# EEM_Connectors.net
KiCad netlist of a schematic drawn in Altium Designer
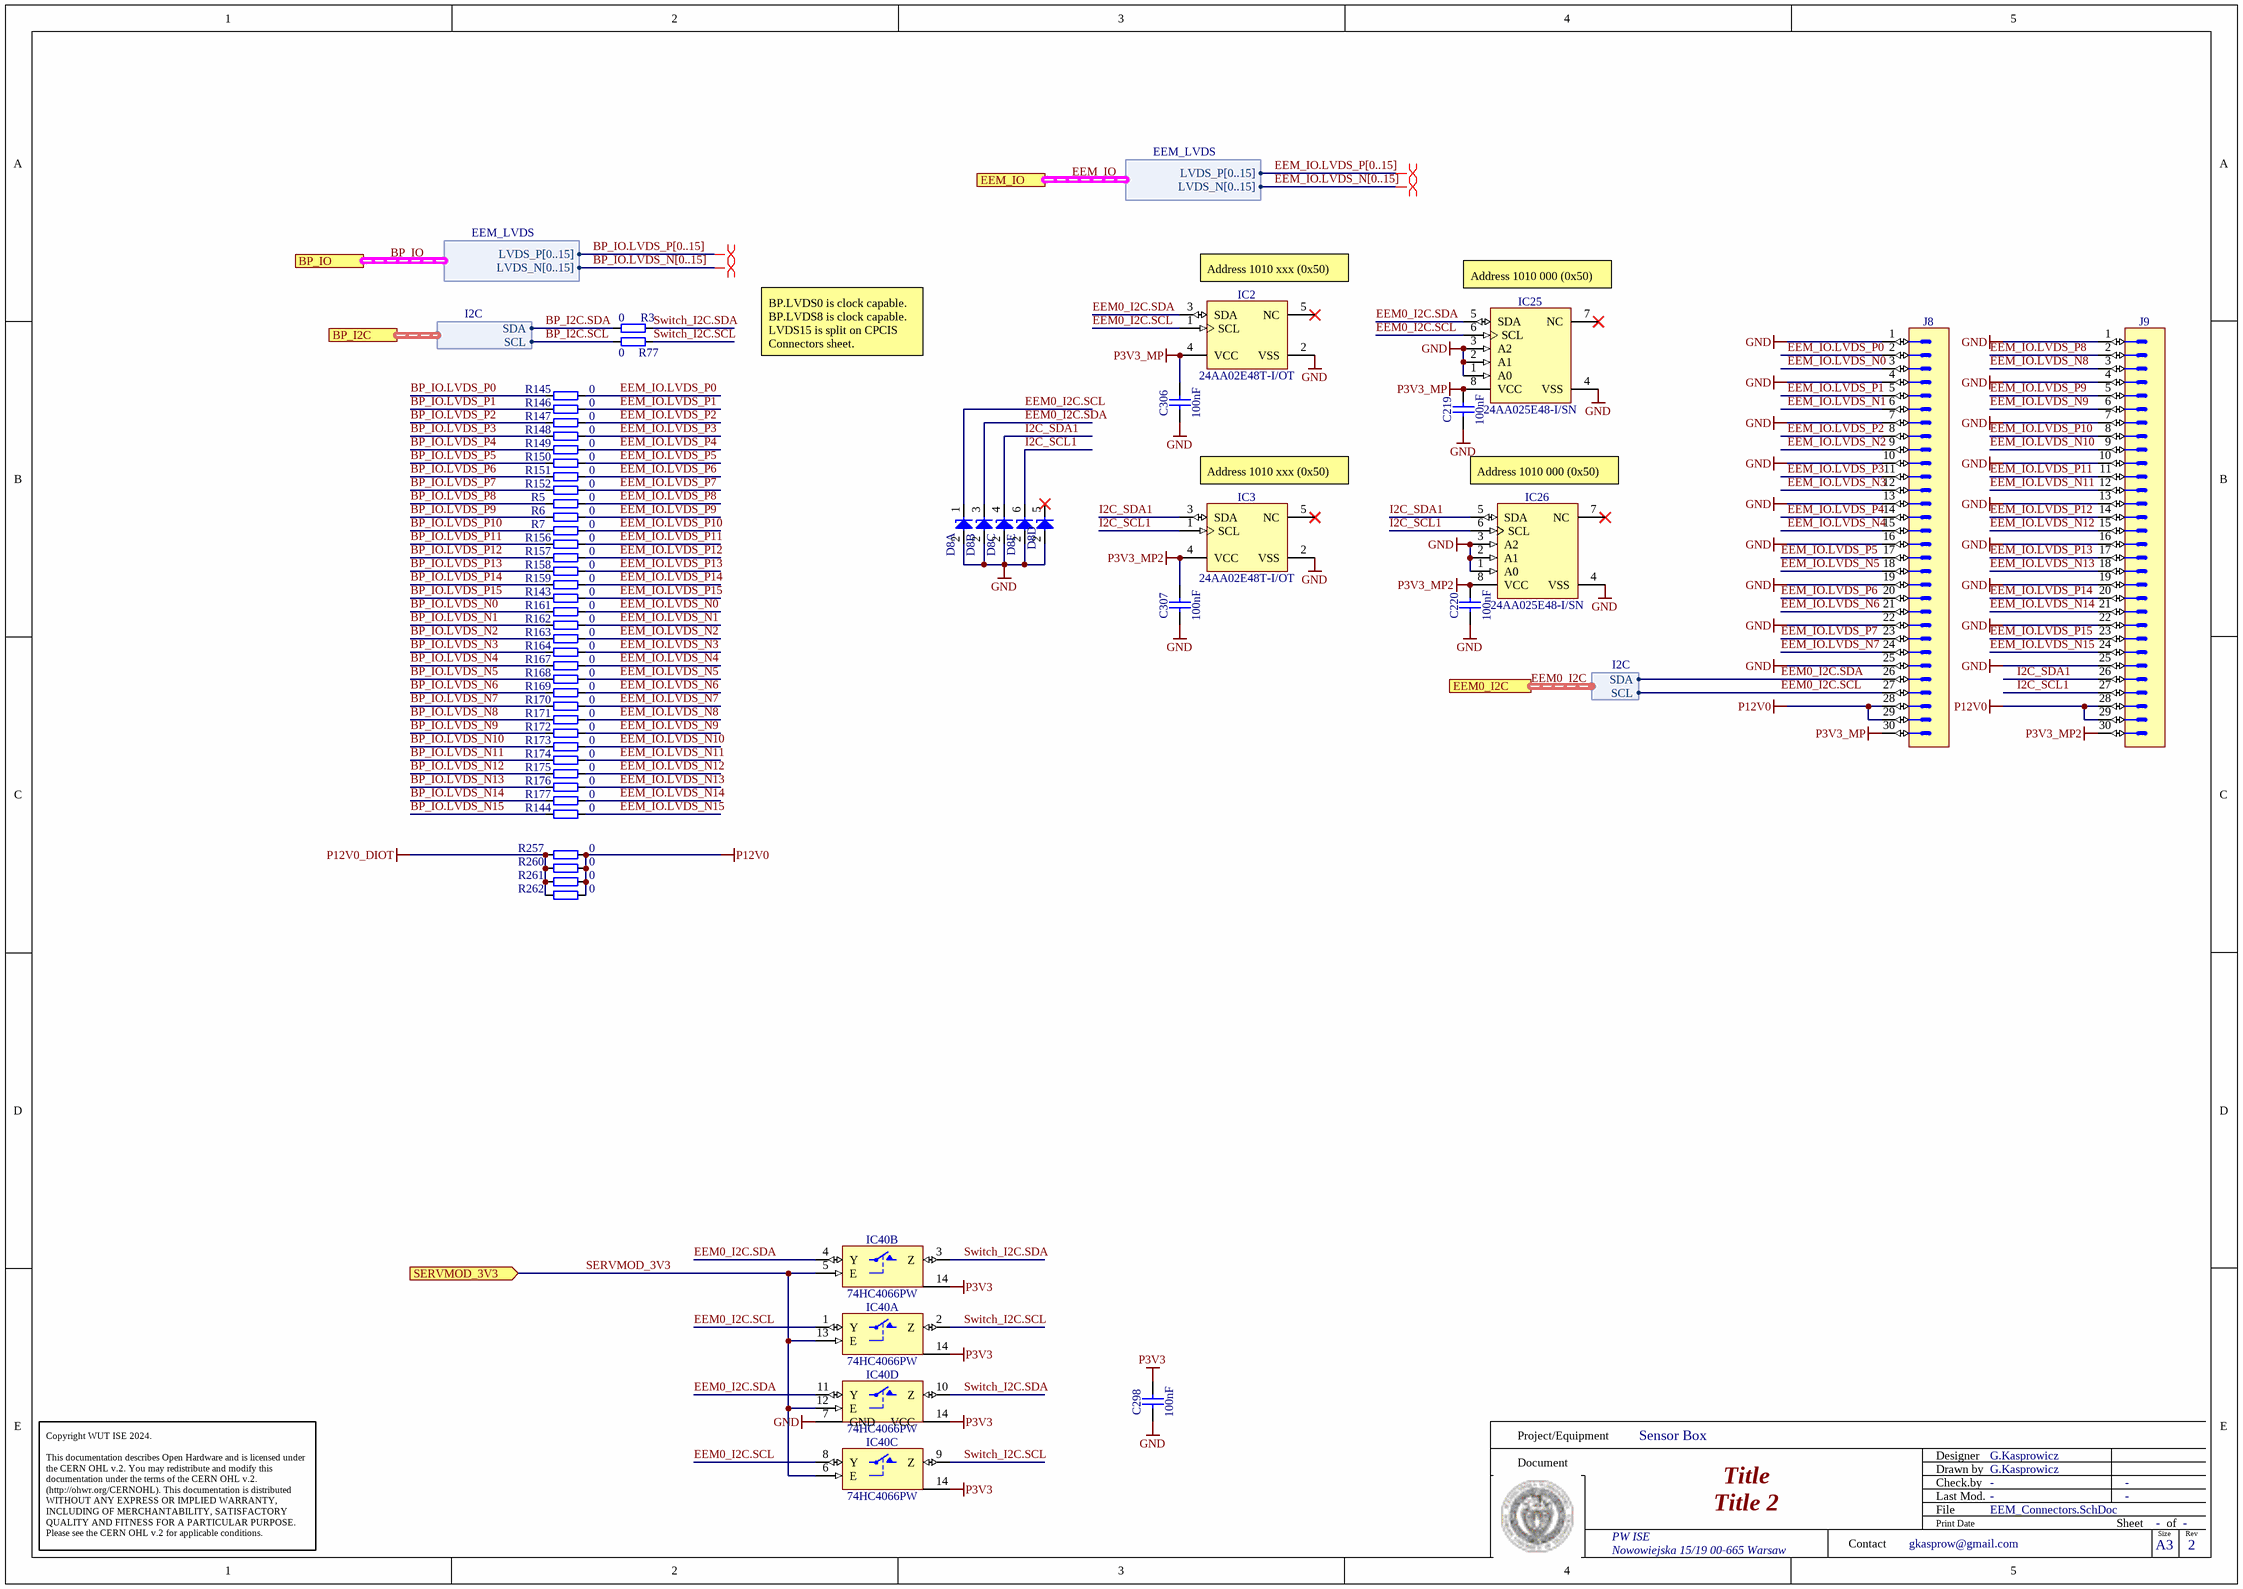
[diagram p0: EEM_Connectors.SchDoc]

(export (version "E")
  (design (tool "Eeschema 10.0.6"))
  (components
    (comp (ref "C219")
      (value "100nF")
      (footprint "CAPC1005X55N")
      (description "Non-polarised capacitor")
      (fields
        (field (name "PART NUMBER") "CC0402_100NF_50V_10%_X7R")
        (field (name "VOLTAGE") "50V")
        (field (name "AUTHOR") "CERN DEM MR")
      )
      (libsource (lib "Capacitors") (part "Capacitor - non polarized"))
    )
    (comp (ref "C220")
      (value "100nF")
      (footprint "CAPC1005X55N")
      (description "Non-polarised capacitor")
      (fields
        (field (name "PART NUMBER") "CC0402_100NF_50V_10%_X7R")
        (field (name "VOLTAGE") "50V")
        (field (name "AUTHOR") "CERN DEM MR")
      )
      (libsource (lib "Capacitors") (part "Capacitor - non polarized"))
    )
    (comp (ref "C298")
      (value "100nF")
      (footprint "CAPC1005X55N")
      (description "Non-polarised capacitor")
      (fields
        (field (name "PART NUMBER") "CC0402_100NF_50V_10%_X7R")
        (field (name "VOLTAGE") "50V")
        (field (name "AUTHOR") "CERN DEM MR")
      )
      (libsource (lib "Capacitors") (part "Capacitor - non polarized"))
    )
    (comp (ref "C306")
      (value "100nF")
      (footprint "CAPC1005X55N")
      (description "Non-polarised capacitor")
      (fields
        (field (name "PART NUMBER") "CC0402_100NF_50V_10%_X7R")
        (field (name "VOLTAGE") "50V")
        (field (name "AUTHOR") "CERN DEM MR")
      )
      (libsource (lib "Capacitors") (part "Capacitor - non polarized"))
    )
    (comp (ref "C307")
      (value "100nF")
      (footprint "CAPC1005X55N")
      (description "Non-polarised capacitor")
      (fields
        (field (name "PART NUMBER") "CC0402_100NF_50V_10%_X7R")
        (field (name "VOLTAGE") "50V")
        (field (name "AUTHOR") "CERN DEM MR")
      )
      (libsource (lib "Capacitors") (part "Capacitor - non polarized"))
    )
    (comp (ref "D8")
      (value "PESD3V3L5UY")
      (footprint "SOT65P210X110-6N")
      (description "Fivefold ESD Protection Diode Arrays")
      (fields
        (field (name "VOLTAGE") "3.3V")
        (field (name "POWER") "200W")
        (field (name "AUTHOR") "CERN DEM WB")
      )
      (libsource (lib "ICs And Semiconductors") (part "PESD Array 5diodes 6pins Common anode2"))
    )
    (comp (ref "IC2")
      (value "24AA02E48T-I/OT")
      (footprint "SOT95P280X145-5N")
      (description "1.7V-5.5V, 2K I2C Serial EEPROM With EUI-48 Node Identity")
      (fields (field (name "MANUFACTURER") "MICROCHIP TECHNOLOGY") (field (name "AUTHOR") "CERN DEM MR"))
      (libsource (lib "ICs And Semiconductors") (part "24AA02E48T-I/OT"))
    )
    (comp (ref "IC3")
      (value "24AA02E48T-I/OT")
      (footprint "SOT95P280X145-5N")
      (description "1.7V-5.5V, 2K I2C Serial EEPROM With EUI-48 Node Identity")
      (fields (field (name "MANUFACTURER") "MICROCHIP TECHNOLOGY") (field (name "AUTHOR") "CERN DEM MR"))
      (libsource (lib "ICs And Semiconductors") (part "24AA02E48T-I/OT"))
    )
    (comp (ref "IC25")
      (value "24AA025E48-I/SN")
      (footprint "SOIC127P600X175-8N")
      (description "1.7V-5.5V, 2K I2C™ Serial EEPROMs with EUI-48™ Node Identity")
      (fields (field (name "MANUFACTURER") "MICROCHIP TECHNOLOGY") (field (name "AUTHOR") "CERN DEM MR"))
      (libsource (lib "ICs And Semiconductors") (part "24AA025E48-I/SN"))
    )
    (comp (ref "IC26")
      (value "24AA025E48-I/SN")
      (footprint "SOIC127P600X175-8N")
      (description "1.7V-5.5V, 2K I2C™ Serial EEPROMs with EUI-48™ Node Identity")
      (fields (field (name "MANUFACTURER") "MICROCHIP TECHNOLOGY") (field (name "AUTHOR") "CERN DEM MR"))
      (libsource (lib "ICs And Semiconductors") (part "24AA025E48-I/SN"))
    )
    (comp (ref "IC40")
      (value "74HC4066PW")
      (footprint "SOP65P640X110-14N")
      (fields (field (name "MANUFACTURER") "NXP SEMICONDUCTORS") (field (name "AUTHOR") "CERN DEM JLC"))
      (libsource (lib "ICs And Semiconductors") (part "4066"))
    )
    (comp (ref "J8")
      (value "~")
      (footprint "3M_N2530-6002RB")
      (description "Connector 30 Male")
      (fields
        (field (name "PART NUMBER") "3M_N2530-6002RB")
        (field (name "MANUFACTURER") "3M")
        (field (name "AUTHOR") "CERN DEM JLC")
      )
      (libsource (lib "Connectors") (part "Connector 30 Male"))
    )
    (comp (ref "J9")
      (value "~")
      (footprint "3M_N2530-6002RB")
      (description "Connector 30 Male")
      (fields
        (field (name "PART NUMBER") "3M_N2530-6002RB")
        (field (name "MANUFACTURER") "3M")
        (field (name "AUTHOR") "CERN DEM JLC")
      )
      (libsource (lib "Connectors") (part "Connector 30 Male"))
    )
    (comp (ref "R3")
      (value "0")
      (footprint "RESC1005X40N")
      (description "Resistor")
      (fields
        (field (name "PART NUMBER") "R0402_0R_JUMPER")
        (field (name "MANUFACTURER") "GENERIC")
        (field (name "AUTHOR") "CERN DEM JLC")
      )
      (libsource (lib "Resistors") (part "Resistor"))
    )
    (comp (ref "R5")
      (value "0")
      (footprint "RESC1005X40N")
      (description "Resistor")
      (fields
        (field (name "PART NUMBER") "R0402_0R_JUMPER")
        (field (name "MANUFACTURER") "GENERIC")
        (field (name "AUTHOR") "CERN DEM JLC")
      )
      (libsource (lib "Resistors") (part "Resistor"))
    )
    (comp (ref "R6")
      (value "0")
      (footprint "RESC1005X40N")
      (description "Resistor")
      (fields
        (field (name "PART NUMBER") "R0402_0R_JUMPER")
        (field (name "MANUFACTURER") "GENERIC")
        (field (name "AUTHOR") "CERN DEM JLC")
      )
      (libsource (lib "Resistors") (part "Resistor"))
    )
    (comp (ref "R7")
      (value "0")
      (footprint "RESC1005X40N")
      (description "Resistor")
      (fields
        (field (name "PART NUMBER") "R0402_0R_JUMPER")
        (field (name "MANUFACTURER") "GENERIC")
        (field (name "AUTHOR") "CERN DEM JLC")
      )
      (libsource (lib "Resistors") (part "Resistor"))
    )
    (comp (ref "R77")
      (value "0")
      (footprint "RESC1005X40N")
      (description "Resistor")
      (fields
        (field (name "PART NUMBER") "R0402_0R_JUMPER")
        (field (name "MANUFACTURER") "GENERIC")
        (field (name "AUTHOR") "CERN DEM JLC")
      )
      (libsource (lib "Resistors") (part "Resistor"))
    )
    (comp (ref "R143")
      (value "0")
      (footprint "RESC1005X40N")
      (description "Resistor")
      (fields
        (field (name "PART NUMBER") "R0402_0R_JUMPER")
        (field (name "MANUFACTURER") "GENERIC")
        (field (name "AUTHOR") "CERN DEM JLC")
      )
      (libsource (lib "Resistors") (part "Resistor"))
    )
    (comp (ref "R144")
      (value "0")
      (footprint "RESC1005X40N")
      (description "Resistor")
      (fields
        (field (name "PART NUMBER") "R0402_0R_JUMPER")
        (field (name "MANUFACTURER") "GENERIC")
        (field (name "AUTHOR") "CERN DEM JLC")
      )
      (libsource (lib "Resistors") (part "Resistor"))
    )
    (comp (ref "R145")
      (value "0")
      (footprint "RESC1005X40N")
      (description "Resistor")
      (fields
        (field (name "PART NUMBER") "R0402_0R_JUMPER")
        (field (name "MANUFACTURER") "GENERIC")
        (field (name "AUTHOR") "CERN DEM JLC")
      )
      (libsource (lib "Resistors") (part "Resistor"))
    )
    (comp (ref "R146")
      (value "0")
      (footprint "RESC1005X40N")
      (description "Resistor")
      (fields
        (field (name "PART NUMBER") "R0402_0R_JUMPER")
        (field (name "MANUFACTURER") "GENERIC")
        (field (name "AUTHOR") "CERN DEM JLC")
      )
      (libsource (lib "Resistors") (part "Resistor"))
    )
    (comp (ref "R147")
      (value "0")
      (footprint "RESC1005X40N")
      (description "Resistor")
      (fields
        (field (name "PART NUMBER") "R0402_0R_JUMPER")
        (field (name "MANUFACTURER") "GENERIC")
        (field (name "AUTHOR") "CERN DEM JLC")
      )
      (libsource (lib "Resistors") (part "Resistor"))
    )
    (comp (ref "R148")
      (value "0")
      (footprint "RESC1005X40N")
      (description "Resistor")
      (fields
        (field (name "PART NUMBER") "R0402_0R_JUMPER")
        (field (name "MANUFACTURER") "GENERIC")
        (field (name "AUTHOR") "CERN DEM JLC")
      )
      (libsource (lib "Resistors") (part "Resistor"))
    )
    (comp (ref "R149")
      (value "0")
      (footprint "RESC1005X40N")
      (description "Resistor")
      (fields
        (field (name "PART NUMBER") "R0402_0R_JUMPER")
        (field (name "MANUFACTURER") "GENERIC")
        (field (name "AUTHOR") "CERN DEM JLC")
      )
      (libsource (lib "Resistors") (part "Resistor"))
    )
    (comp (ref "R150")
      (value "0")
      (footprint "RESC1005X40N")
      (description "Resistor")
      (fields
        (field (name "PART NUMBER") "R0402_0R_JUMPER")
        (field (name "MANUFACTURER") "GENERIC")
        (field (name "AUTHOR") "CERN DEM JLC")
      )
      (libsource (lib "Resistors") (part "Resistor"))
    )
    (comp (ref "R151")
      (value "0")
      (footprint "RESC1005X40N")
      (description "Resistor")
      (fields
        (field (name "PART NUMBER") "R0402_0R_JUMPER")
        (field (name "MANUFACTURER") "GENERIC")
        (field (name "AUTHOR") "CERN DEM JLC")
      )
      (libsource (lib "Resistors") (part "Resistor"))
    )
    (comp (ref "R152")
      (value "0")
      (footprint "RESC1005X40N")
      (description "Resistor")
      (fields
        (field (name "PART NUMBER") "R0402_0R_JUMPER")
        (field (name "MANUFACTURER") "GENERIC")
        (field (name "AUTHOR") "CERN DEM JLC")
      )
      (libsource (lib "Resistors") (part "Resistor"))
    )
    (comp (ref "R156")
      (value "0")
      (footprint "RESC1005X40N")
      (description "Resistor")
      (fields
        (field (name "PART NUMBER") "R0402_0R_JUMPER")
        (field (name "MANUFACTURER") "GENERIC")
        (field (name "AUTHOR") "CERN DEM JLC")
      )
      (libsource (lib "Resistors") (part "Resistor"))
    )
    (comp (ref "R157")
      (value "0")
      (footprint "RESC1005X40N")
      (description "Resistor")
      (fields
        (field (name "PART NUMBER") "R0402_0R_JUMPER")
        (field (name "MANUFACTURER") "GENERIC")
        (field (name "AUTHOR") "CERN DEM JLC")
      )
      (libsource (lib "Resistors") (part "Resistor"))
    )
    (comp (ref "R158")
      (value "0")
      (footprint "RESC1005X40N")
      (description "Resistor")
      (fields
        (field (name "PART NUMBER") "R0402_0R_JUMPER")
        (field (name "MANUFACTURER") "GENERIC")
        (field (name "AUTHOR") "CERN DEM JLC")
      )
      (libsource (lib "Resistors") (part "Resistor"))
    )
    (comp (ref "R159")
      (value "0")
      (footprint "RESC1005X40N")
      (description "Resistor")
      (fields
        (field (name "PART NUMBER") "R0402_0R_JUMPER")
        (field (name "MANUFACTURER") "GENERIC")
        (field (name "AUTHOR") "CERN DEM JLC")
      )
      (libsource (lib "Resistors") (part "Resistor"))
    )
    (comp (ref "R161")
      (value "0")
      (footprint "RESC1005X40N")
      (description "Resistor")
      (fields
        (field (name "PART NUMBER") "R0402_0R_JUMPER")
        (field (name "MANUFACTURER") "GENERIC")
        (field (name "AUTHOR") "CERN DEM JLC")
      )
      (libsource (lib "Resistors") (part "Resistor"))
    )
    (comp (ref "R162")
      (value "0")
      (footprint "RESC1005X40N")
      (description "Resistor")
      (fields
        (field (name "PART NUMBER") "R0402_0R_JUMPER")
        (field (name "MANUFACTURER") "GENERIC")
        (field (name "AUTHOR") "CERN DEM JLC")
      )
      (libsource (lib "Resistors") (part "Resistor"))
    )
    (comp (ref "R163")
      (value "0")
      (footprint "RESC1005X40N")
      (description "Resistor")
      (fields
        (field (name "PART NUMBER") "R0402_0R_JUMPER")
        (field (name "MANUFACTURER") "GENERIC")
        (field (name "AUTHOR") "CERN DEM JLC")
      )
      (libsource (lib "Resistors") (part "Resistor"))
    )
    (comp (ref "R164")
      (value "0")
      (footprint "RESC1005X40N")
      (description "Resistor")
      (fields
        (field (name "PART NUMBER") "R0402_0R_JUMPER")
        (field (name "MANUFACTURER") "GENERIC")
        (field (name "AUTHOR") "CERN DEM JLC")
      )
      (libsource (lib "Resistors") (part "Resistor"))
    )
    (comp (ref "R167")
      (value "0")
      (footprint "RESC1005X40N")
      (description "Resistor")
      (fields
        (field (name "PART NUMBER") "R0402_0R_JUMPER")
        (field (name "MANUFACTURER") "GENERIC")
        (field (name "AUTHOR") "CERN DEM JLC")
      )
      (libsource (lib "Resistors") (part "Resistor"))
    )
    (comp (ref "R168")
      (value "0")
      (footprint "RESC1005X40N")
      (description "Resistor")
      (fields
        (field (name "PART NUMBER") "R0402_0R_JUMPER")
        (field (name "MANUFACTURER") "GENERIC")
        (field (name "AUTHOR") "CERN DEM JLC")
      )
      (libsource (lib "Resistors") (part "Resistor"))
    )
    (comp (ref "R169")
      (value "0")
      (footprint "RESC1005X40N")
      (description "Resistor")
      (fields
        (field (name "PART NUMBER") "R0402_0R_JUMPER")
        (field (name "MANUFACTURER") "GENERIC")
        (field (name "AUTHOR") "CERN DEM JLC")
      )
      (libsource (lib "Resistors") (part "Resistor"))
    )
    (comp (ref "R170")
      (value "0")
      (footprint "RESC1005X40N")
      (description "Resistor")
      (fields
        (field (name "PART NUMBER") "R0402_0R_JUMPER")
        (field (name "MANUFACTURER") "GENERIC")
        (field (name "AUTHOR") "CERN DEM JLC")
      )
      (libsource (lib "Resistors") (part "Resistor"))
    )
    (comp (ref "R171")
      (value "0")
      (footprint "RESC1005X40N")
      (description "Resistor")
      (fields
        (field (name "PART NUMBER") "R0402_0R_JUMPER")
        (field (name "MANUFACTURER") "GENERIC")
        (field (name "AUTHOR") "CERN DEM JLC")
      )
      (libsource (lib "Resistors") (part "Resistor"))
    )
    (comp (ref "R172")
      (value "0")
      (footprint "RESC1005X40N")
      (description "Resistor")
      (fields
        (field (name "PART NUMBER") "R0402_0R_JUMPER")
        (field (name "MANUFACTURER") "GENERIC")
        (field (name "AUTHOR") "CERN DEM JLC")
      )
      (libsource (lib "Resistors") (part "Resistor"))
    )
    (comp (ref "R173")
      (value "0")
      (footprint "RESC1005X40N")
      (description "Resistor")
      (fields
        (field (name "PART NUMBER") "R0402_0R_JUMPER")
        (field (name "MANUFACTURER") "GENERIC")
        (field (name "AUTHOR") "CERN DEM JLC")
      )
      (libsource (lib "Resistors") (part "Resistor"))
    )
    (comp (ref "R174")
      (value "0")
      (footprint "RESC1005X40N")
      (description "Resistor")
      (fields
        (field (name "PART NUMBER") "R0402_0R_JUMPER")
        (field (name "MANUFACTURER") "GENERIC")
        (field (name "AUTHOR") "CERN DEM JLC")
      )
      (libsource (lib "Resistors") (part "Resistor"))
    )
    (comp (ref "R175")
      (value "0")
      (footprint "RESC1005X40N")
      (description "Resistor")
      (fields
        (field (name "PART NUMBER") "R0402_0R_JUMPER")
        (field (name "MANUFACTURER") "GENERIC")
        (field (name "AUTHOR") "CERN DEM JLC")
      )
      (libsource (lib "Resistors") (part "Resistor"))
    )
    (comp (ref "R176")
      (value "0")
      (footprint "RESC1005X40N")
      (description "Resistor")
      (fields
        (field (name "PART NUMBER") "R0402_0R_JUMPER")
        (field (name "MANUFACTURER") "GENERIC")
        (field (name "AUTHOR") "CERN DEM JLC")
      )
      (libsource (lib "Resistors") (part "Resistor"))
    )
    (comp (ref "R177")
      (value "0")
      (footprint "RESC1005X40N")
      (description "Resistor")
      (fields
        (field (name "PART NUMBER") "R0402_0R_JUMPER")
        (field (name "MANUFACTURER") "GENERIC")
        (field (name "AUTHOR") "CERN DEM JLC")
      )
      (libsource (lib "Resistors") (part "Resistor"))
    )
    (comp (ref "R257")
      (value "0")
      (footprint "RESC1005X40N")
      (description "Resistor")
      (fields
        (field (name "PART NUMBER") "R0402_0R_JUMPER")
        (field (name "MANUFACTURER") "GENERIC")
        (field (name "AUTHOR") "CERN DEM JLC")
      )
      (libsource (lib "Resistors") (part "Resistor"))
    )
    (comp (ref "R260")
      (value "0")
      (footprint "RESC1005X40N")
      (description "Resistor")
      (fields
        (field (name "PART NUMBER") "R0402_0R_JUMPER")
        (field (name "MANUFACTURER") "GENERIC")
        (field (name "AUTHOR") "CERN DEM JLC")
      )
      (libsource (lib "Resistors") (part "Resistor"))
    )
    (comp (ref "R261")
      (value "0")
      (footprint "RESC1005X40N")
      (description "Resistor")
      (fields
        (field (name "PART NUMBER") "R0402_0R_JUMPER")
        (field (name "MANUFACTURER") "GENERIC")
        (field (name "AUTHOR") "CERN DEM JLC")
      )
      (libsource (lib "Resistors") (part "Resistor"))
    )
    (comp (ref "R262")
      (value "0")
      (footprint "RESC1005X40N")
      (description "Resistor")
      (fields
        (field (name "PART NUMBER") "R0402_0R_JUMPER")
        (field (name "MANUFACTURER") "GENERIC")
        (field (name "AUTHOR") "CERN DEM JLC")
      )
      (libsource (lib "Resistors") (part "Resistor"))
    )
  )
  (nets
    (net (code "5") (name "/BP_I2C.SCL") (class "Default")
      (node (ref "R77") (pin "1") (pinfunction "1_1") (pintype "passive"))
    )
    (net (code "6") (name "/BP_I2C.SDA") (class "Default")
      (node (ref "R3") (pin "1") (pinfunction "1_1") (pintype "passive"))
    )
    (net (code "7") (name "/BP_IO.LVDS_N0") (class "Default")
      (node (ref "R161") (pin "1") (pinfunction "1_1") (pintype "passive"))
    )
    (net (code "8") (name "/BP_IO.LVDS_N1") (class "Default")
      (node (ref "R162") (pin "1") (pinfunction "1_1") (pintype "passive"))
    )
    (net (code "9") (name "/BP_IO.LVDS_N2") (class "Default")
      (node (ref "R163") (pin "1") (pinfunction "1_1") (pintype "passive"))
    )
    (net (code "10") (name "/BP_IO.LVDS_N3") (class "Default")
      (node (ref "R164") (pin "1") (pinfunction "1_1") (pintype "passive"))
    )
    (net (code "11") (name "/BP_IO.LVDS_N4") (class "Default")
      (node (ref "R167") (pin "1") (pinfunction "1_1") (pintype "passive"))
    )
    (net (code "12") (name "/BP_IO.LVDS_N5") (class "Default")
      (node (ref "R168") (pin "1") (pinfunction "1_1") (pintype "passive"))
    )
    (net (code "13") (name "/BP_IO.LVDS_N6") (class "Default")
      (node (ref "R169") (pin "1") (pinfunction "1_1") (pintype "passive"))
    )
    (net (code "14") (name "/BP_IO.LVDS_N7") (class "Default")
      (node (ref "R170") (pin "1") (pinfunction "1_1") (pintype "passive"))
    )
    (net (code "15") (name "/BP_IO.LVDS_N8") (class "Default")
      (node (ref "R171") (pin "1") (pinfunction "1_1") (pintype "passive"))
    )
    (net (code "16") (name "/BP_IO.LVDS_N9") (class "Default")
      (node (ref "R172") (pin "1") (pinfunction "1_1") (pintype "passive"))
    )
    (net (code "17") (name "/BP_IO.LVDS_N10") (class "Default")
      (node (ref "R173") (pin "1") (pinfunction "1_1") (pintype "passive"))
    )
    (net (code "18") (name "/BP_IO.LVDS_N11") (class "Default")
      (node (ref "R174") (pin "1") (pinfunction "1_1") (pintype "passive"))
    )
    (net (code "19") (name "/BP_IO.LVDS_N12") (class "Default")
      (node (ref "R175") (pin "1") (pinfunction "1_1") (pintype "passive"))
    )
    (net (code "20") (name "/BP_IO.LVDS_N13") (class "Default")
      (node (ref "R176") (pin "1") (pinfunction "1_1") (pintype "passive"))
    )
    (net (code "21") (name "/BP_IO.LVDS_N14") (class "Default")
      (node (ref "R177") (pin "1") (pinfunction "1_1") (pintype "passive"))
    )
    (net (code "22") (name "/BP_IO.LVDS_N15") (class "Default")
      (node (ref "R144") (pin "2") (pinfunction "2_2") (pintype "passive"))
    )
    (net (code "23") (name "/BP_IO.LVDS_P0") (class "Default")
      (node (ref "R145") (pin "1") (pinfunction "1_1") (pintype "passive"))
    )
    (net (code "24") (name "/BP_IO.LVDS_P1") (class "Default")
      (node (ref "R146") (pin "1") (pinfunction "1_1") (pintype "passive"))
    )
    (net (code "25") (name "/BP_IO.LVDS_P2") (class "Default")
      (node (ref "R147") (pin "1") (pinfunction "1_1") (pintype "passive"))
    )
    (net (code "26") (name "/BP_IO.LVDS_P3") (class "Default")
      (node (ref "R148") (pin "1") (pinfunction "1_1") (pintype "passive"))
    )
    (net (code "27") (name "/BP_IO.LVDS_P4") (class "Default")
      (node (ref "R149") (pin "1") (pinfunction "1_1") (pintype "passive"))
    )
    (net (code "28") (name "/BP_IO.LVDS_P5") (class "Default")
      (node (ref "R150") (pin "1") (pinfunction "1_1") (pintype "passive"))
    )
    (net (code "29") (name "/BP_IO.LVDS_P6") (class "Default")
      (node (ref "R151") (pin "1") (pinfunction "1_1") (pintype "passive"))
    )
    (net (code "30") (name "/BP_IO.LVDS_P7") (class "Default")
      (node (ref "R152") (pin "1") (pinfunction "1_1") (pintype "passive"))
    )
    (net (code "31") (name "/BP_IO.LVDS_P8") (class "Default")
      (node (ref "R5") (pin "1") (pinfunction "1_1") (pintype "passive"))
    )
    (net (code "32") (name "/BP_IO.LVDS_P9") (class "Default")
      (node (ref "R6") (pin "1") (pinfunction "1_1") (pintype "passive"))
    )
    (net (code "33") (name "/BP_IO.LVDS_P10") (class "Default")
      (node (ref "R7") (pin "1") (pinfunction "1_1") (pintype "passive"))
    )
    (net (code "34") (name "/BP_IO.LVDS_P11") (class "Default")
      (node (ref "R156") (pin "1") (pinfunction "1_1") (pintype "passive"))
    )
    (net (code "35") (name "/BP_IO.LVDS_P12") (class "Default")
      (node (ref "R157") (pin "1") (pinfunction "1_1") (pintype "passive"))
    )
    (net (code "36") (name "/BP_IO.LVDS_P13") (class "Default")
      (node (ref "R158") (pin "1") (pinfunction "1_1") (pintype "passive"))
    )
    (net (code "37") (name "/BP_IO.LVDS_P14") (class "Default")
      (node (ref "R159") (pin "1") (pinfunction "1_1") (pintype "passive"))
    )
    (net (code "38") (name "/BP_IO.LVDS_P15") (class "Default")
      (node (ref "R143") (pin "2") (pinfunction "2_2") (pintype "passive"))
    )
    (net (code "40") (name "/EEM0_I2C.SCL") (class "Default")
      (node (ref "D8") (pin "1") (pinfunction "C_1") (pintype "passive"))
      (node (ref "IC2") (pin "1") (pinfunction "SCL_1") (pintype "input"))
      (node (ref "IC25") (pin "6") (pinfunction "SCL_6") (pintype "input"))
      (node (ref "IC40") (pin "1") (pinfunction "Y_1") (pintype "bidirectional"))
      (node (ref "IC40") (pin "8") (pinfunction "Y_8") (pintype "bidirectional"))
      (node (ref "J8") (pin "27") (pinfunction "27_27") (pintype "bidirectional"))
    )
    (net (code "41") (name "/EEM0_I2C.SDA") (class "Default")
      (node (ref "D8") (pin "3") (pinfunction "C_3") (pintype "passive"))
      (node (ref "IC2") (pin "3") (pinfunction "SDA_3") (pintype "bidirectional"))
      (node (ref "IC25") (pin "5") (pinfunction "SDA_5") (pintype "bidirectional"))
      (node (ref "IC40") (pin "11") (pinfunction "Y_11") (pintype "bidirectional"))
      (node (ref "IC40") (pin "4") (pinfunction "Y_4") (pintype "bidirectional"))
      (node (ref "J8") (pin "26") (pinfunction "26_26") (pintype "bidirectional"))
    )
    (net (code "43") (name "/EEM_IO.LVDS_N0") (class "Default")
      (node (ref "J8") (pin "3") (pinfunction "3_3") (pintype "bidirectional"))
      (node (ref "R161") (pin "2") (pinfunction "2_2") (pintype "passive"))
    )
    (net (code "44") (name "/EEM_IO.LVDS_N1") (class "Default")
      (node (ref "J8") (pin "6") (pinfunction "6_6") (pintype "bidirectional"))
      (node (ref "R162") (pin "2") (pinfunction "2_2") (pintype "passive"))
    )
    (net (code "45") (name "/EEM_IO.LVDS_N2") (class "Default")
      (node (ref "J8") (pin "9") (pinfunction "9_9") (pintype "bidirectional"))
      (node (ref "R163") (pin "2") (pinfunction "2_2") (pintype "passive"))
    )
    (net (code "46") (name "/EEM_IO.LVDS_N3") (class "Default")
      (node (ref "J8") (pin "12") (pinfunction "12_12") (pintype "bidirectional"))
      (node (ref "R164") (pin "2") (pinfunction "2_2") (pintype "passive"))
    )
    (net (code "47") (name "/EEM_IO.LVDS_N4") (class "Default")
      (node (ref "J8") (pin "15") (pinfunction "15_15") (pintype "bidirectional"))
      (node (ref "R167") (pin "2") (pinfunction "2_2") (pintype "passive"))
    )
    (net (code "48") (name "/EEM_IO.LVDS_N5") (class "Default")
      (node (ref "J8") (pin "18") (pinfunction "18_18") (pintype "bidirectional"))
      (node (ref "R168") (pin "2") (pinfunction "2_2") (pintype "passive"))
    )
    (net (code "49") (name "/EEM_IO.LVDS_N6") (class "Default")
      (node (ref "J8") (pin "21") (pinfunction "21_21") (pintype "bidirectional"))
      (node (ref "R169") (pin "2") (pinfunction "2_2") (pintype "passive"))
    )
    (net (code "50") (name "/EEM_IO.LVDS_N7") (class "Default")
      (node (ref "J8") (pin "24") (pinfunction "24_24") (pintype "bidirectional"))
      (node (ref "R170") (pin "2") (pinfunction "2_2") (pintype "passive"))
    )
    (net (code "51") (name "/EEM_IO.LVDS_N8") (class "Default")
      (node (ref "J9") (pin "3") (pinfunction "3_3") (pintype "bidirectional"))
      (node (ref "R171") (pin "2") (pinfunction "2_2") (pintype "passive"))
    )
    (net (code "52") (name "/EEM_IO.LVDS_N9") (class "Default")
      (node (ref "J9") (pin "6") (pinfunction "6_6") (pintype "bidirectional"))
      (node (ref "R172") (pin "2") (pinfunction "2_2") (pintype "passive"))
    )
    (net (code "53") (name "/EEM_IO.LVDS_N10") (class "Default")
      (node (ref "J9") (pin "9") (pinfunction "9_9") (pintype "bidirectional"))
      (node (ref "R173") (pin "2") (pinfunction "2_2") (pintype "passive"))
    )
    (net (code "54") (name "/EEM_IO.LVDS_N11") (class "Default")
      (node (ref "J9") (pin "12") (pinfunction "12_12") (pintype "bidirectional"))
      (node (ref "R174") (pin "2") (pinfunction "2_2") (pintype "passive"))
    )
    (net (code "55") (name "/EEM_IO.LVDS_N12") (class "Default")
      (node (ref "J9") (pin "15") (pinfunction "15_15") (pintype "bidirectional"))
      (node (ref "R175") (pin "2") (pinfunction "2_2") (pintype "passive"))
    )
    (net (code "56") (name "/EEM_IO.LVDS_N13") (class "Default")
      (node (ref "J9") (pin "18") (pinfunction "18_18") (pintype "bidirectional"))
      (node (ref "R176") (pin "2") (pinfunction "2_2") (pintype "passive"))
    )
    (net (code "57") (name "/EEM_IO.LVDS_N14") (class "Default")
      (node (ref "J9") (pin "21") (pinfunction "21_21") (pintype "bidirectional"))
      (node (ref "R177") (pin "2") (pinfunction "2_2") (pintype "passive"))
    )
    (net (code "58") (name "/EEM_IO.LVDS_N15") (class "Default")
      (node (ref "J9") (pin "24") (pinfunction "24_24") (pintype "bidirectional"))
      (node (ref "R144") (pin "1") (pinfunction "1_1") (pintype "passive"))
    )
    (net (code "60") (name "/EEM_IO.LVDS_P0") (class "Default")
      (node (ref "J8") (pin "2") (pinfunction "2_2") (pintype "bidirectional"))
      (node (ref "R145") (pin "2") (pinfunction "2_2") (pintype "passive"))
    )
    (net (code "61") (name "/EEM_IO.LVDS_P1") (class "Default")
      (node (ref "J8") (pin "5") (pinfunction "5_5") (pintype "bidirectional"))
      (node (ref "R146") (pin "2") (pinfunction "2_2") (pintype "passive"))
    )
    (net (code "62") (name "/EEM_IO.LVDS_P2") (class "Default")
      (node (ref "J8") (pin "8") (pinfunction "8_8") (pintype "bidirectional"))
      (node (ref "R147") (pin "2") (pinfunction "2_2") (pintype "passive"))
    )
    (net (code "63") (name "/EEM_IO.LVDS_P3") (class "Default")
      (node (ref "J8") (pin "11") (pinfunction "11_11") (pintype "bidirectional"))
      (node (ref "R148") (pin "2") (pinfunction "2_2") (pintype "passive"))
    )
    (net (code "64") (name "/EEM_IO.LVDS_P4") (class "Default")
      (node (ref "J8") (pin "14") (pinfunction "14_14") (pintype "bidirectional"))
      (node (ref "R149") (pin "2") (pinfunction "2_2") (pintype "passive"))
    )
    (net (code "65") (name "/EEM_IO.LVDS_P5") (class "Default")
      (node (ref "J8") (pin "17") (pinfunction "17_17") (pintype "bidirectional"))
      (node (ref "R150") (pin "2") (pinfunction "2_2") (pintype "passive"))
    )
    (net (code "66") (name "/EEM_IO.LVDS_P6") (class "Default")
      (node (ref "J8") (pin "20") (pinfunction "20_20") (pintype "bidirectional"))
      (node (ref "R151") (pin "2") (pinfunction "2_2") (pintype "passive"))
    )
    (net (code "67") (name "/EEM_IO.LVDS_P7") (class "Default")
      (node (ref "J8") (pin "23") (pinfunction "23_23") (pintype "bidirectional"))
      (node (ref "R152") (pin "2") (pinfunction "2_2") (pintype "passive"))
    )
    (net (code "68") (name "/EEM_IO.LVDS_P8") (class "Default")
      (node (ref "J9") (pin "2") (pinfunction "2_2") (pintype "bidirectional"))
      (node (ref "R5") (pin "2") (pinfunction "2_2") (pintype "passive"))
    )
    (net (code "69") (name "/EEM_IO.LVDS_P9") (class "Default")
      (node (ref "J9") (pin "5") (pinfunction "5_5") (pintype "bidirectional"))
      (node (ref "R6") (pin "2") (pinfunction "2_2") (pintype "passive"))
    )
    (net (code "70") (name "/EEM_IO.LVDS_P10") (class "Default")
      (node (ref "J9") (pin "8") (pinfunction "8_8") (pintype "bidirectional"))
      (node (ref "R7") (pin "2") (pinfunction "2_2") (pintype "passive"))
    )
    (net (code "71") (name "/EEM_IO.LVDS_P11") (class "Default")
      (node (ref "J9") (pin "11") (pinfunction "11_11") (pintype "bidirectional"))
      (node (ref "R156") (pin "2") (pinfunction "2_2") (pintype "passive"))
    )
    (net (code "72") (name "/EEM_IO.LVDS_P12") (class "Default")
      (node (ref "J9") (pin "14") (pinfunction "14_14") (pintype "bidirectional"))
      (node (ref "R157") (pin "2") (pinfunction "2_2") (pintype "passive"))
    )
    (net (code "73") (name "/EEM_IO.LVDS_P13") (class "Default")
      (node (ref "J9") (pin "17") (pinfunction "17_17") (pintype "bidirectional"))
      (node (ref "R158") (pin "2") (pinfunction "2_2") (pintype "passive"))
    )
    (net (code "74") (name "/EEM_IO.LVDS_P14") (class "Default")
      (node (ref "J9") (pin "20") (pinfunction "20_20") (pintype "bidirectional"))
      (node (ref "R159") (pin "2") (pinfunction "2_2") (pintype "passive"))
    )
    (net (code "75") (name "/EEM_IO.LVDS_P15") (class "Default")
      (node (ref "J9") (pin "23") (pinfunction "23_23") (pintype "bidirectional"))
      (node (ref "R143") (pin "1") (pinfunction "1_1") (pintype "passive"))
    )
    (net (code "78") (name "/I2C_SCL1") (class "Default")
      (node (ref "D8") (pin "6") (pinfunction "C_6") (pintype "passive"))
      (node (ref "IC26") (pin "6") (pinfunction "SCL_6") (pintype "input"))
      (node (ref "IC3") (pin "1") (pinfunction "SCL_1") (pintype "input"))
      (node (ref "J9") (pin "27") (pinfunction "27_27") (pintype "bidirectional"))
    )
    (net (code "79") (name "/I2C_SDA1") (class "Default")
      (node (ref "D8") (pin "4") (pinfunction "C_4") (pintype "passive"))
      (node (ref "IC26") (pin "5") (pinfunction "SDA_5") (pintype "bidirectional"))
      (node (ref "IC3") (pin "3") (pinfunction "SDA_3") (pintype "bidirectional"))
      (node (ref "J9") (pin "26") (pinfunction "26_26") (pintype "bidirectional"))
    )
    (net (code "80") (name "/SERVMOD_3V3") (class "Default")
      (node (ref "IC40") (pin "12") (pinfunction "E_12") (pintype "input"))
      (node (ref "IC40") (pin "13") (pinfunction "E_13") (pintype "input"))
      (node (ref "IC40") (pin "5") (pinfunction "E_5") (pintype "input"))
      (node (ref "IC40") (pin "6") (pinfunction "E_6") (pintype "input"))
    )
    (net (code "81") (name "/Switch_I2C.SCL") (class "Default")
      (node (ref "IC40") (pin "2") (pinfunction "Z_2") (pintype "bidirectional"))
      (node (ref "IC40") (pin "9") (pinfunction "Z_9") (pintype "bidirectional"))
      (node (ref "R77") (pin "2") (pinfunction "2_2") (pintype "passive"))
    )
    (net (code "82") (name "/Switch_I2C.SDA") (class "Default")
      (node (ref "IC40") (pin "10") (pinfunction "Z_10") (pintype "bidirectional"))
      (node (ref "IC40") (pin "3") (pinfunction "Z_3") (pintype "bidirectional"))
      (node (ref "R3") (pin "2") (pinfunction "2_2") (pintype "passive"))
    )
    (net (code "85") (name "GND") (class "Default")
      (node (ref "C219") (pin "1") (pinfunction "1_1") (pintype "passive"))
      (node (ref "C220") (pin "1") (pinfunction "1_1") (pintype "passive"))
      (node (ref "C298") (pin "1") (pinfunction "1_1") (pintype "passive"))
      (node (ref "C306") (pin "1") (pinfunction "1_1") (pintype "passive"))
      (node (ref "C307") (pin "1") (pinfunction "1_1") (pintype "passive"))
      (node (ref "D8") (pin "2") (pinfunction "A_2") (pintype "passive"))
      (node (ref "IC2") (pin "2") (pinfunction "VSS_2") (pintype "power_in"))
      (node (ref "IC25") (pin "1") (pinfunction "A0_1") (pintype "input"))
      (node (ref "IC25") (pin "2") (pinfunction "A1_2") (pintype "input"))
      (node (ref "IC25") (pin "3") (pinfunction "A2_3") (pintype "input"))
      (node (ref "IC25") (pin "4") (pinfunction "VSS_4") (pintype "power_in"))
      (node (ref "IC26") (pin "1") (pinfunction "A0_1") (pintype "input"))
      (node (ref "IC26") (pin "2") (pinfunction "A1_2") (pintype "input"))
      (node (ref "IC26") (pin "3") (pinfunction "A2_3") (pintype "input"))
      (node (ref "IC26") (pin "4") (pinfunction "VSS_4") (pintype "power_in"))
      (node (ref "IC3") (pin "2") (pinfunction "VSS_2") (pintype "power_in"))
      (node (ref "IC40") (pin "7") (pinfunction "GND_7") (pintype "power_in"))
      (node (ref "J8") (pin "1") (pinfunction "1_1") (pintype "bidirectional"))
      (node (ref "J8") (pin "10") (pinfunction "10_10") (pintype "bidirectional"))
      (node (ref "J8") (pin "13") (pinfunction "13_13") (pintype "bidirectional"))
      (node (ref "J8") (pin "16") (pinfunction "16_16") (pintype "bidirectional"))
      (node (ref "J8") (pin "19") (pinfunction "19_19") (pintype "bidirectional"))
      (node (ref "J8") (pin "22") (pinfunction "22_22") (pintype "bidirectional"))
      (node (ref "J8") (pin "25") (pinfunction "25_25") (pintype "bidirectional"))
      (node (ref "J8") (pin "4") (pinfunction "4_4") (pintype "bidirectional"))
      (node (ref "J8") (pin "7") (pinfunction "7_7") (pintype "bidirectional"))
      (node (ref "J9") (pin "1") (pinfunction "1_1") (pintype "bidirectional"))
      (node (ref "J9") (pin "10") (pinfunction "10_10") (pintype "bidirectional"))
      (node (ref "J9") (pin "13") (pinfunction "13_13") (pintype "bidirectional"))
      (node (ref "J9") (pin "16") (pinfunction "16_16") (pintype "bidirectional"))
      (node (ref "J9") (pin "19") (pinfunction "19_19") (pintype "bidirectional"))
      (node (ref "J9") (pin "22") (pinfunction "22_22") (pintype "bidirectional"))
      (node (ref "J9") (pin "25") (pinfunction "25_25") (pintype "bidirectional"))
      (node (ref "J9") (pin "4") (pinfunction "4_4") (pintype "bidirectional"))
      (node (ref "J9") (pin "7") (pinfunction "7_7") (pintype "bidirectional"))
    )
    (net (code "86") (name "P3V3") (class "Default")
      (node (ref "C298") (pin "2") (pinfunction "2_2") (pintype "passive"))
      (node (ref "IC40") (pin "14") (pinfunction "VCC_14") (pintype "power_in"))
    )
    (net (code "87") (name "P3V3_MP") (class "Default")
      (node (ref "C219") (pin "2") (pinfunction "2_2") (pintype "passive"))
      (node (ref "C306") (pin "2") (pinfunction "2_2") (pintype "passive"))
      (node (ref "IC2") (pin "4") (pinfunction "VCC_4") (pintype "power_in"))
      (node (ref "IC25") (pin "8") (pinfunction "VCC_8") (pintype "power_in"))
      (node (ref "J8") (pin "30") (pinfunction "30_30") (pintype "bidirectional"))
    )
    (net (code "88") (name "P3V3_MP2") (class "Default")
      (node (ref "C220") (pin "2") (pinfunction "2_2") (pintype "passive"))
      (node (ref "C307") (pin "2") (pinfunction "2_2") (pintype "passive"))
      (node (ref "IC26") (pin "8") (pinfunction "VCC_8") (pintype "power_in"))
      (node (ref "IC3") (pin "4") (pinfunction "VCC_4") (pintype "power_in"))
      (node (ref "J9") (pin "30") (pinfunction "30_30") (pintype "bidirectional"))
    )
    (net (code "89") (name "P12V0") (class "Default")
      (node (ref "J8") (pin "28") (pinfunction "28_28") (pintype "bidirectional"))
      (node (ref "J8") (pin "29") (pinfunction "29_29") (pintype "bidirectional"))
      (node (ref "J9") (pin "28") (pinfunction "28_28") (pintype "bidirectional"))
      (node (ref "J9") (pin "29") (pinfunction "29_29") (pintype "bidirectional"))
      (node (ref "R257") (pin "2") (pinfunction "2_2") (pintype "passive"))
      (node (ref "R260") (pin "2") (pinfunction "2_2") (pintype "passive"))
      (node (ref "R261") (pin "2") (pinfunction "2_2") (pintype "passive"))
      (node (ref "R262") (pin "2") (pinfunction "2_2") (pintype "passive"))
    )
    (net (code "90") (name "P12V0_DIOT") (class "Default")
      (node (ref "R257") (pin "1") (pinfunction "1_1") (pintype "passive"))
      (node (ref "R260") (pin "1") (pinfunction "1_1") (pintype "passive"))
      (node (ref "R261") (pin "1") (pinfunction "1_1") (pintype "passive"))
      (node (ref "R262") (pin "1") (pinfunction "1_1") (pintype "passive"))
    )
    (net (code "91") (name "unconnected-(D8D-C-Pad5)") (class "Default")
      (node (ref "D8") (pin "5") (pinfunction "C_5") (pintype "passive+no_connect"))
    )
    (net (code "92") (name "unconnected-(IC2-NC-Pad5)") (class "Default")
      (node (ref "IC2") (pin "5") (pinfunction "NC_5") (pintype "passive+no_connect"))
    )
    (net (code "93") (name "unconnected-(IC3-NC-Pad5)") (class "Default")
      (node (ref "IC3") (pin "5") (pinfunction "NC_5") (pintype "passive+no_connect"))
    )
    (net (code "94") (name "unconnected-(IC25-NC-Pad7)") (class "Default")
      (node (ref "IC25") (pin "7") (pinfunction "NC_7") (pintype "passive+no_connect"))
    )
    (net (code "95") (name "unconnected-(IC26-NC-Pad7)") (class "Default")
      (node (ref "IC26") (pin "7") (pinfunction "NC_7") (pintype "passive+no_connect"))
    )
  )
)
